# 20260112.net
KiCad netlist of a schematic drawn in EasyEDA Pro
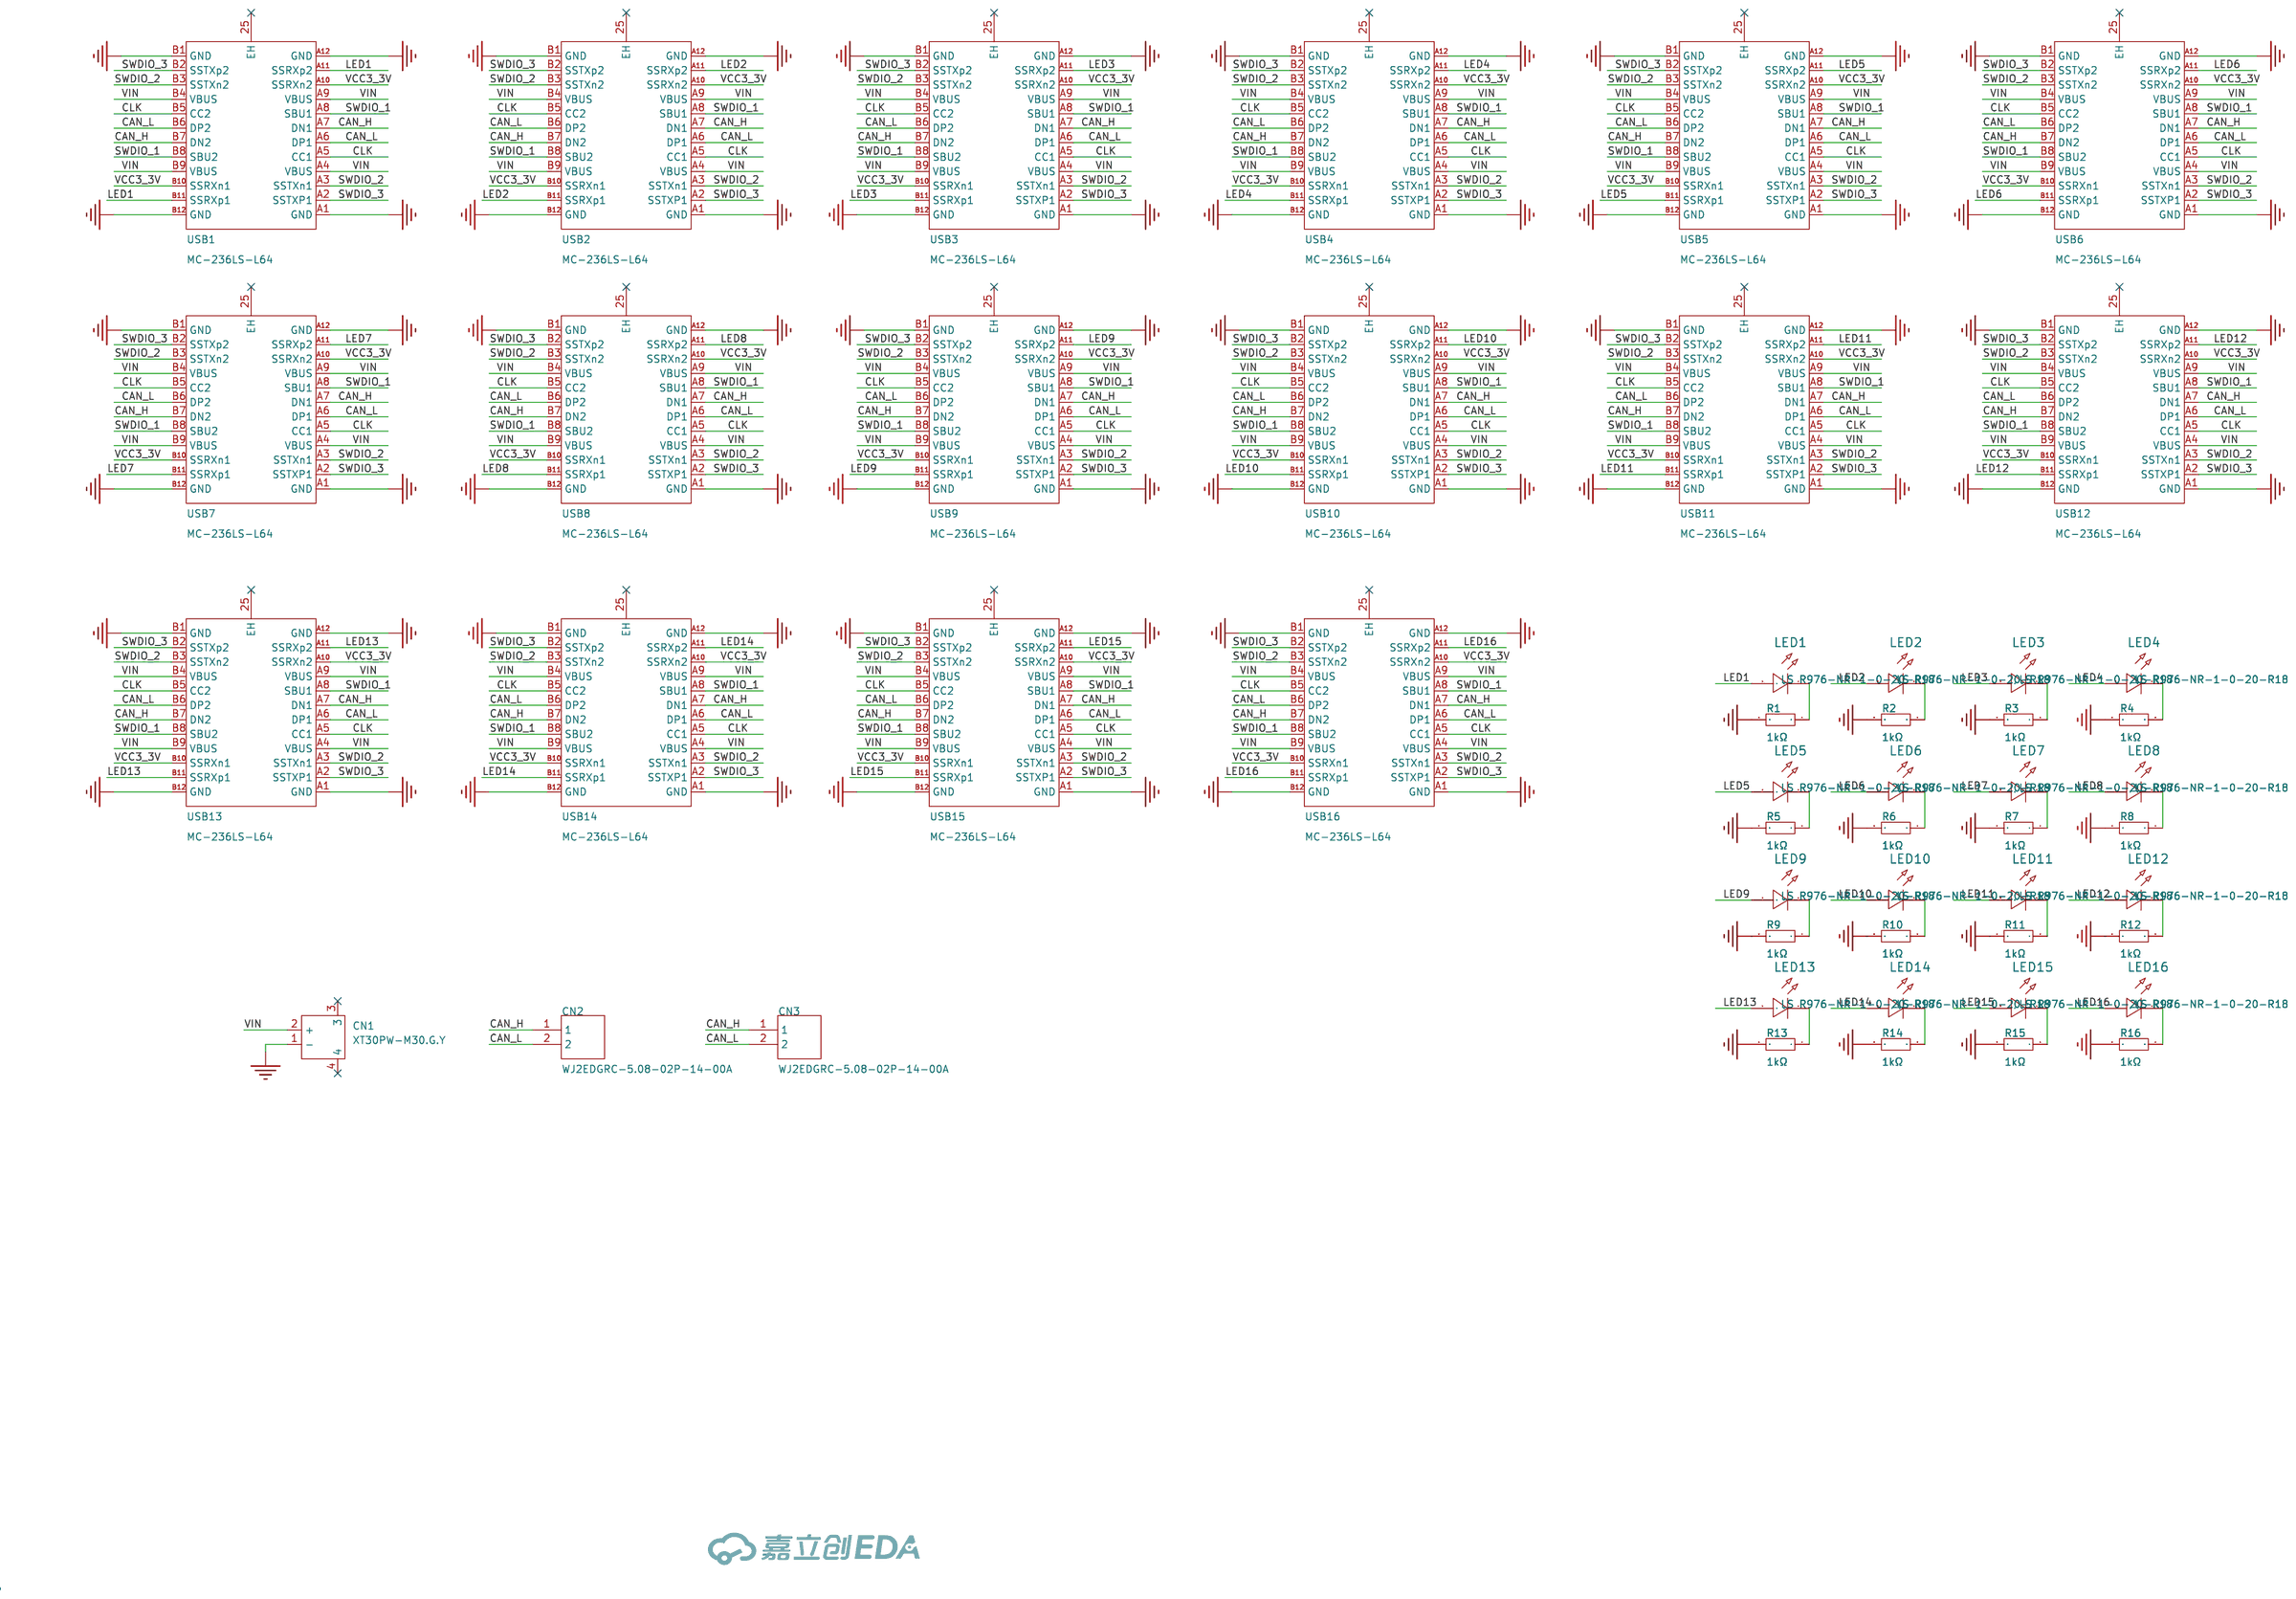
[diagram p0: schematic sheet]

(export (version "E")
  (design (tool "Eeschema 10.0.6"))
  (components
    (comp (ref "CN1")
      (value "XT30PW-M30.G.Y")
      (footprint "easyedapro:CONN-TH_XT30PW-M")
      (description "类别:-;类型1:-;")
      (fields (field (name "Manufacturer") "AMASS(艾迈斯)"))
      (libsource (lib "easyedapro") (part "XT30PW-M"))
    )
    (comp (ref "CN2")
      (value "WJ2EDGRC-5.08-02P-14-00A")
      (footprint "easyedapro:CONN-TH_2P-P5.08_WJ2EDGRC-5.08-2P")
      (fields (field (name "Manufacturer") "KANGNEX(康奈克斯电气)"))
      (libsource (lib "easyedapro") (part "WJ2EDGRC-5.08-2P"))
    )
    (comp (ref "CN3")
      (value "WJ2EDGRC-5.08-02P-14-00A")
      (footprint "easyedapro:CONN-TH_2P-P5.08_WJ2EDGRC-5.08-2P")
      (fields (field (name "Manufacturer") "KANGNEX(康奈克斯电气)"))
      (libsource (lib "easyedapro") (part "WJ2EDGRC-5.08-2P"))
    )
    (comp (ref "LED1")
      (value "LS R976-NR-1-0-20-R18")
      (footprint "easyedapro:LED_0805")
      (fields (field (name "Manufacturer") "OSRAM(欧司朗)"))
      (libsource (lib "easyedapro") (part "LED_R"))
    )
    (comp (ref "LED2")
      (value "LS R976-NR-1-0-20-R18")
      (footprint "easyedapro:LED_0805")
      (fields (field (name "Manufacturer") "OSRAM(欧司朗)"))
      (libsource (lib "easyedapro") (part "LED_R"))
    )
    (comp (ref "LED3")
      (value "LS R976-NR-1-0-20-R18")
      (footprint "easyedapro:LED_0805")
      (fields (field (name "Manufacturer") "OSRAM(欧司朗)"))
      (libsource (lib "easyedapro") (part "LED_R"))
    )
    (comp (ref "LED4")
      (value "LS R976-NR-1-0-20-R18")
      (footprint "easyedapro:LED_0805")
      (fields (field (name "Manufacturer") "OSRAM(欧司朗)"))
      (libsource (lib "easyedapro") (part "LED_R"))
    )
    (comp (ref "LED5")
      (value "LS R976-NR-1-0-20-R18")
      (footprint "easyedapro:LED_0805")
      (fields (field (name "Manufacturer") "OSRAM(欧司朗)"))
      (libsource (lib "easyedapro") (part "LED_R"))
    )
    (comp (ref "LED6")
      (value "LS R976-NR-1-0-20-R18")
      (footprint "easyedapro:LED_0805")
      (fields (field (name "Manufacturer") "OSRAM(欧司朗)"))
      (libsource (lib "easyedapro") (part "LED_R"))
    )
    (comp (ref "LED7")
      (value "LS R976-NR-1-0-20-R18")
      (footprint "easyedapro:LED_0805")
      (fields (field (name "Manufacturer") "OSRAM(欧司朗)"))
      (libsource (lib "easyedapro") (part "LED_R"))
    )
    (comp (ref "LED8")
      (value "LS R976-NR-1-0-20-R18")
      (footprint "easyedapro:LED_0805")
      (fields (field (name "Manufacturer") "OSRAM(欧司朗)"))
      (libsource (lib "easyedapro") (part "LED_R"))
    )
    (comp (ref "LED9")
      (value "LS R976-NR-1-0-20-R18")
      (footprint "easyedapro:LED_0805")
      (fields (field (name "Manufacturer") "OSRAM(欧司朗)"))
      (libsource (lib "easyedapro") (part "LED_R"))
    )
    (comp (ref "LED10")
      (value "LS R976-NR-1-0-20-R18")
      (footprint "easyedapro:LED_0805")
      (fields (field (name "Manufacturer") "OSRAM(欧司朗)"))
      (libsource (lib "easyedapro") (part "LED_R"))
    )
    (comp (ref "LED11")
      (value "LS R976-NR-1-0-20-R18")
      (footprint "easyedapro:LED_0805")
      (fields (field (name "Manufacturer") "OSRAM(欧司朗)"))
      (libsource (lib "easyedapro") (part "LED_R"))
    )
    (comp (ref "LED12")
      (value "LS R976-NR-1-0-20-R18")
      (footprint "easyedapro:LED_0805")
      (fields (field (name "Manufacturer") "OSRAM(欧司朗)"))
      (libsource (lib "easyedapro") (part "LED_R"))
    )
    (comp (ref "LED13")
      (value "LS R976-NR-1-0-20-R18")
      (footprint "easyedapro:LED_0805")
      (fields (field (name "Manufacturer") "OSRAM(欧司朗)"))
      (libsource (lib "easyedapro") (part "LED_R"))
    )
    (comp (ref "LED14")
      (value "LS R976-NR-1-0-20-R18")
      (footprint "easyedapro:LED_0805")
      (fields (field (name "Manufacturer") "OSRAM(欧司朗)"))
      (libsource (lib "easyedapro") (part "LED_R"))
    )
    (comp (ref "LED15")
      (value "LS R976-NR-1-0-20-R18")
      (footprint "easyedapro:LED_0805")
      (fields (field (name "Manufacturer") "OSRAM(欧司朗)"))
      (libsource (lib "easyedapro") (part "LED_R"))
    )
    (comp (ref "LED16")
      (value "LS R976-NR-1-0-20-R18")
      (footprint "easyedapro:LED_0805")
      (fields (field (name "Manufacturer") "OSRAM(欧司朗)"))
      (libsource (lib "easyedapro") (part "LED_R"))
    )
    (comp (ref "R1")
      (value "1kΩ")
      (footprint "easyedapro:R0805")
      (fields
        (field (name "Manufacturer Part") "0805W8F1001T5E")
        (field (name "Manufacturer") "UNI-ROYAL(厚声)")
      )
      (libsource (lib "easyedapro") (part "电阻"))
    )
    (comp (ref "R2")
      (value "1kΩ")
      (footprint "easyedapro:R0805")
      (fields
        (field (name "Manufacturer Part") "0805W8F1001T5E")
        (field (name "Manufacturer") "UNI-ROYAL(厚声)")
      )
      (libsource (lib "easyedapro") (part "电阻"))
    )
    (comp (ref "R3")
      (value "1kΩ")
      (footprint "easyedapro:R0805")
      (fields
        (field (name "Manufacturer Part") "0805W8F1001T5E")
        (field (name "Manufacturer") "UNI-ROYAL(厚声)")
      )
      (libsource (lib "easyedapro") (part "电阻"))
    )
    (comp (ref "R4")
      (value "1kΩ")
      (footprint "easyedapro:R0805")
      (fields
        (field (name "Manufacturer Part") "0805W8F1001T5E")
        (field (name "Manufacturer") "UNI-ROYAL(厚声)")
      )
      (libsource (lib "easyedapro") (part "电阻"))
    )
    (comp (ref "R5")
      (value "1kΩ")
      (footprint "easyedapro:R0805")
      (fields
        (field (name "Manufacturer Part") "0805W8F1001T5E")
        (field (name "Manufacturer") "UNI-ROYAL(厚声)")
      )
      (libsource (lib "easyedapro") (part "电阻"))
    )
    (comp (ref "R6")
      (value "1kΩ")
      (footprint "easyedapro:R0805")
      (fields
        (field (name "Manufacturer Part") "0805W8F1001T5E")
        (field (name "Manufacturer") "UNI-ROYAL(厚声)")
      )
      (libsource (lib "easyedapro") (part "电阻"))
    )
    (comp (ref "R7")
      (value "1kΩ")
      (footprint "easyedapro:R0805")
      (fields
        (field (name "Manufacturer Part") "0805W8F1001T5E")
        (field (name "Manufacturer") "UNI-ROYAL(厚声)")
      )
      (libsource (lib "easyedapro") (part "电阻"))
    )
    (comp (ref "R8")
      (value "1kΩ")
      (footprint "easyedapro:R0805")
      (fields
        (field (name "Manufacturer Part") "0805W8F1001T5E")
        (field (name "Manufacturer") "UNI-ROYAL(厚声)")
      )
      (libsource (lib "easyedapro") (part "电阻"))
    )
    (comp (ref "R9")
      (value "1kΩ")
      (footprint "easyedapro:R0805")
      (fields
        (field (name "Manufacturer Part") "0805W8F1001T5E")
        (field (name "Manufacturer") "UNI-ROYAL(厚声)")
      )
      (libsource (lib "easyedapro") (part "电阻"))
    )
    (comp (ref "R10")
      (value "1kΩ")
      (footprint "easyedapro:R0805")
      (fields
        (field (name "Manufacturer Part") "0805W8F1001T5E")
        (field (name "Manufacturer") "UNI-ROYAL(厚声)")
      )
      (libsource (lib "easyedapro") (part "电阻"))
    )
    (comp (ref "R11")
      (value "1kΩ")
      (footprint "easyedapro:R0805")
      (fields
        (field (name "Manufacturer Part") "0805W8F1001T5E")
        (field (name "Manufacturer") "UNI-ROYAL(厚声)")
      )
      (libsource (lib "easyedapro") (part "电阻"))
    )
    (comp (ref "R12")
      (value "1kΩ")
      (footprint "easyedapro:R0805")
      (fields
        (field (name "Manufacturer Part") "0805W8F1001T5E")
        (field (name "Manufacturer") "UNI-ROYAL(厚声)")
      )
      (libsource (lib "easyedapro") (part "电阻"))
    )
    (comp (ref "R13")
      (value "1kΩ")
      (footprint "easyedapro:R0805")
      (fields
        (field (name "Manufacturer Part") "0805W8F1001T5E")
        (field (name "Manufacturer") "UNI-ROYAL(厚声)")
      )
      (libsource (lib "easyedapro") (part "电阻"))
    )
    (comp (ref "R14")
      (value "1kΩ")
      (footprint "easyedapro:R0805")
      (fields
        (field (name "Manufacturer Part") "0805W8F1001T5E")
        (field (name "Manufacturer") "UNI-ROYAL(厚声)")
      )
      (libsource (lib "easyedapro") (part "电阻"))
    )
    (comp (ref "R15")
      (value "1kΩ")
      (footprint "easyedapro:R0805")
      (fields
        (field (name "Manufacturer Part") "0805W8F1001T5E")
        (field (name "Manufacturer") "UNI-ROYAL(厚声)")
      )
      (libsource (lib "easyedapro") (part "电阻"))
    )
    (comp (ref "R16")
      (value "1kΩ")
      (footprint "easyedapro:R0805")
      (fields
        (field (name "Manufacturer Part") "0805W8F1001T5E")
        (field (name "Manufacturer") "UNI-ROYAL(厚声)")
      )
      (libsource (lib "easyedapro") (part "电阻"))
    )
    (comp (ref "USB1")
      (value "MC-236LS-L64")
      (footprint "easyedapro:TYPE-C-USB-SMD_TYPE-C-31-M-06")
      (description "连接器类型:Type-C;协议标准:USB 3.1;公母:母;安装方式:立贴;触点数量:24P;端口数量:1;额定电流 - 电源:5A;工作温度:-25°C~+85°C;")
      (fields (field (name "Manufacturer") "HANBO(汉博)"))
      (libsource (lib "easyedapro") (part "MC-236LS-L64"))
    )
    (comp (ref "USB2")
      (value "MC-236LS-L64")
      (footprint "easyedapro:TYPE-C-USB-SMD_TYPE-C-31-M-06")
      (description "连接器类型:Type-C;协议标准:USB 3.1;公母:母;安装方式:立贴;触点数量:24P;端口数量:1;额定电流 - 电源:5A;工作温度:-25°C~+85°C;")
      (fields (field (name "Manufacturer") "HANBO(汉博)"))
      (libsource (lib "easyedapro") (part "MC-236LS-L64"))
    )
    (comp (ref "USB3")
      (value "MC-236LS-L64")
      (footprint "easyedapro:TYPE-C-USB-SMD_TYPE-C-31-M-06")
      (description "连接器类型:Type-C;协议标准:USB 3.1;公母:母;安装方式:立贴;触点数量:24P;端口数量:1;额定电流 - 电源:5A;工作温度:-25°C~+85°C;")
      (fields (field (name "Manufacturer") "HANBO(汉博)"))
      (libsource (lib "easyedapro") (part "MC-236LS-L64"))
    )
    (comp (ref "USB4")
      (value "MC-236LS-L64")
      (footprint "easyedapro:TYPE-C-USB-SMD_TYPE-C-31-M-06")
      (description "连接器类型:Type-C;协议标准:USB 3.1;公母:母;安装方式:立贴;触点数量:24P;端口数量:1;额定电流 - 电源:5A;工作温度:-25°C~+85°C;")
      (fields (field (name "Manufacturer") "HANBO(汉博)"))
      (libsource (lib "easyedapro") (part "MC-236LS-L64"))
    )
    (comp (ref "USB5")
      (value "MC-236LS-L64")
      (footprint "easyedapro:TYPE-C-USB-SMD_TYPE-C-31-M-06")
      (description "连接器类型:Type-C;协议标准:USB 3.1;公母:母;安装方式:立贴;触点数量:24P;端口数量:1;额定电流 - 电源:5A;工作温度:-25°C~+85°C;")
      (fields (field (name "Manufacturer") "HANBO(汉博)"))
      (libsource (lib "easyedapro") (part "MC-236LS-L64"))
    )
    (comp (ref "USB6")
      (value "MC-236LS-L64")
      (footprint "easyedapro:TYPE-C-USB-SMD_TYPE-C-31-M-06")
      (description "连接器类型:Type-C;协议标准:USB 3.1;公母:母;安装方式:立贴;触点数量:24P;端口数量:1;额定电流 - 电源:5A;工作温度:-25°C~+85°C;")
      (fields (field (name "Manufacturer") "HANBO(汉博)"))
      (libsource (lib "easyedapro") (part "MC-236LS-L64"))
    )
    (comp (ref "USB7")
      (value "MC-236LS-L64")
      (footprint "easyedapro:TYPE-C-USB-SMD_TYPE-C-31-M-06")
      (description "连接器类型:Type-C;协议标准:USB 3.1;公母:母;安装方式:立贴;触点数量:24P;端口数量:1;额定电流 - 电源:5A;工作温度:-25°C~+85°C;")
      (fields (field (name "Manufacturer") "HANBO(汉博)"))
      (libsource (lib "easyedapro") (part "MC-236LS-L64"))
    )
    (comp (ref "USB8")
      (value "MC-236LS-L64")
      (footprint "easyedapro:TYPE-C-USB-SMD_TYPE-C-31-M-06")
      (description "连接器类型:Type-C;协议标准:USB 3.1;公母:母;安装方式:立贴;触点数量:24P;端口数量:1;额定电流 - 电源:5A;工作温度:-25°C~+85°C;")
      (fields (field (name "Manufacturer") "HANBO(汉博)"))
      (libsource (lib "easyedapro") (part "MC-236LS-L64"))
    )
    (comp (ref "USB9")
      (value "MC-236LS-L64")
      (footprint "easyedapro:TYPE-C-USB-SMD_TYPE-C-31-M-06")
      (description "连接器类型:Type-C;协议标准:USB 3.1;公母:母;安装方式:立贴;触点数量:24P;端口数量:1;额定电流 - 电源:5A;工作温度:-25°C~+85°C;")
      (fields (field (name "Manufacturer") "HANBO(汉博)"))
      (libsource (lib "easyedapro") (part "MC-236LS-L64"))
    )
    (comp (ref "USB10")
      (value "MC-236LS-L64")
      (footprint "easyedapro:TYPE-C-USB-SMD_TYPE-C-31-M-06")
      (description "连接器类型:Type-C;协议标准:USB 3.1;公母:母;安装方式:立贴;触点数量:24P;端口数量:1;额定电流 - 电源:5A;工作温度:-25°C~+85°C;")
      (fields (field (name "Manufacturer") "HANBO(汉博)"))
      (libsource (lib "easyedapro") (part "MC-236LS-L64"))
    )
    (comp (ref "USB11")
      (value "MC-236LS-L64")
      (footprint "easyedapro:TYPE-C-USB-SMD_TYPE-C-31-M-06")
      (description "连接器类型:Type-C;协议标准:USB 3.1;公母:母;安装方式:立贴;触点数量:24P;端口数量:1;额定电流 - 电源:5A;工作温度:-25°C~+85°C;")
      (fields (field (name "Manufacturer") "HANBO(汉博)"))
      (libsource (lib "easyedapro") (part "MC-236LS-L64"))
    )
    (comp (ref "USB12")
      (value "MC-236LS-L64")
      (footprint "easyedapro:TYPE-C-USB-SMD_TYPE-C-31-M-06")
      (description "连接器类型:Type-C;协议标准:USB 3.1;公母:母;安装方式:立贴;触点数量:24P;端口数量:1;额定电流 - 电源:5A;工作温度:-25°C~+85°C;")
      (fields (field (name "Manufacturer") "HANBO(汉博)"))
      (libsource (lib "easyedapro") (part "MC-236LS-L64"))
    )
    (comp (ref "USB13")
      (value "MC-236LS-L64")
      (footprint "easyedapro:TYPE-C-USB-SMD_TYPE-C-31-M-06")
      (description "连接器类型:Type-C;协议标准:USB 3.1;公母:母;安装方式:立贴;触点数量:24P;端口数量:1;额定电流 - 电源:5A;工作温度:-25°C~+85°C;")
      (fields (field (name "Manufacturer") "HANBO(汉博)"))
      (libsource (lib "easyedapro") (part "MC-236LS-L64"))
    )
    (comp (ref "USB14")
      (value "MC-236LS-L64")
      (footprint "easyedapro:TYPE-C-USB-SMD_TYPE-C-31-M-06")
      (description "连接器类型:Type-C;协议标准:USB 3.1;公母:母;安装方式:立贴;触点数量:24P;端口数量:1;额定电流 - 电源:5A;工作温度:-25°C~+85°C;")
      (fields (field (name "Manufacturer") "HANBO(汉博)"))
      (libsource (lib "easyedapro") (part "MC-236LS-L64"))
    )
    (comp (ref "USB15")
      (value "MC-236LS-L64")
      (footprint "easyedapro:TYPE-C-USB-SMD_TYPE-C-31-M-06")
      (description "连接器类型:Type-C;协议标准:USB 3.1;公母:母;安装方式:立贴;触点数量:24P;端口数量:1;额定电流 - 电源:5A;工作温度:-25°C~+85°C;")
      (fields (field (name "Manufacturer") "HANBO(汉博)"))
      (libsource (lib "easyedapro") (part "MC-236LS-L64"))
    )
    (comp (ref "USB16")
      (value "MC-236LS-L64")
      (footprint "easyedapro:TYPE-C-USB-SMD_TYPE-C-31-M-06")
      (description "连接器类型:Type-C;协议标准:USB 3.1;公母:母;安装方式:立贴;触点数量:24P;端口数量:1;额定电流 - 电源:5A;工作温度:-25°C~+85°C;")
      (fields (field (name "Manufacturer") "HANBO(汉博)"))
      (libsource (lib "easyedapro") (part "MC-236LS-L64"))
    )
  )
  (nets
    (net (code "1") (name "/CAN_H") (class "Default")
      (node (ref "CN2") (pin "1") (pinfunction "1_1") (pintype "unspecified"))
      (node (ref "CN3") (pin "1") (pinfunction "1_1") (pintype "unspecified"))
      (node (ref "USB1") (pin "A7") (pinfunction "DN1_A7") (pintype "unspecified"))
      (node (ref "USB1") (pin "B7") (pinfunction "DN2_B7") (pintype "unspecified"))
      (node (ref "USB10") (pin "A7") (pinfunction "DN1_A7") (pintype "unspecified"))
      (node (ref "USB10") (pin "B7") (pinfunction "DN2_B7") (pintype "unspecified"))
      (node (ref "USB11") (pin "A7") (pinfunction "DN1_A7") (pintype "unspecified"))
      (node (ref "USB11") (pin "B7") (pinfunction "DN2_B7") (pintype "unspecified"))
      (node (ref "USB12") (pin "A7") (pinfunction "DN1_A7") (pintype "unspecified"))
      (node (ref "USB12") (pin "B7") (pinfunction "DN2_B7") (pintype "unspecified"))
      (node (ref "USB13") (pin "A7") (pinfunction "DN1_A7") (pintype "unspecified"))
      (node (ref "USB13") (pin "B7") (pinfunction "DN2_B7") (pintype "unspecified"))
      (node (ref "USB14") (pin "A7") (pinfunction "DN1_A7") (pintype "unspecified"))
      (node (ref "USB14") (pin "B7") (pinfunction "DN2_B7") (pintype "unspecified"))
      (node (ref "USB15") (pin "A7") (pinfunction "DN1_A7") (pintype "unspecified"))
      (node (ref "USB15") (pin "B7") (pinfunction "DN2_B7") (pintype "unspecified"))
      (node (ref "USB16") (pin "A7") (pinfunction "DN1_A7") (pintype "unspecified"))
      (node (ref "USB16") (pin "B7") (pinfunction "DN2_B7") (pintype "unspecified"))
      (node (ref "USB2") (pin "A7") (pinfunction "DN1_A7") (pintype "unspecified"))
      (node (ref "USB2") (pin "B7") (pinfunction "DN2_B7") (pintype "unspecified"))
      (node (ref "USB3") (pin "A7") (pinfunction "DN1_A7") (pintype "unspecified"))
      (node (ref "USB3") (pin "B7") (pinfunction "DN2_B7") (pintype "unspecified"))
      (node (ref "USB4") (pin "A7") (pinfunction "DN1_A7") (pintype "unspecified"))
      (node (ref "USB4") (pin "B7") (pinfunction "DN2_B7") (pintype "unspecified"))
      (node (ref "USB5") (pin "A7") (pinfunction "DN1_A7") (pintype "unspecified"))
      (node (ref "USB5") (pin "B7") (pinfunction "DN2_B7") (pintype "unspecified"))
      (node (ref "USB6") (pin "A7") (pinfunction "DN1_A7") (pintype "unspecified"))
      (node (ref "USB6") (pin "B7") (pinfunction "DN2_B7") (pintype "unspecified"))
      (node (ref "USB7") (pin "A7") (pinfunction "DN1_A7") (pintype "unspecified"))
      (node (ref "USB7") (pin "B7") (pinfunction "DN2_B7") (pintype "unspecified"))
      (node (ref "USB8") (pin "A7") (pinfunction "DN1_A7") (pintype "unspecified"))
      (node (ref "USB8") (pin "B7") (pinfunction "DN2_B7") (pintype "unspecified"))
      (node (ref "USB9") (pin "A7") (pinfunction "DN1_A7") (pintype "unspecified"))
      (node (ref "USB9") (pin "B7") (pinfunction "DN2_B7") (pintype "unspecified"))
    )
    (net (code "2") (name "/CAN_L") (class "Default")
      (node (ref "CN2") (pin "2") (pinfunction "2_2") (pintype "unspecified"))
      (node (ref "CN3") (pin "2") (pinfunction "2_2") (pintype "unspecified"))
      (node (ref "USB1") (pin "A6") (pinfunction "DP1_A6") (pintype "unspecified"))
      (node (ref "USB1") (pin "B6") (pinfunction "DP2_B6") (pintype "unspecified"))
      (node (ref "USB10") (pin "A6") (pinfunction "DP1_A6") (pintype "unspecified"))
      (node (ref "USB10") (pin "B6") (pinfunction "DP2_B6") (pintype "unspecified"))
      (node (ref "USB11") (pin "A6") (pinfunction "DP1_A6") (pintype "unspecified"))
      (node (ref "USB11") (pin "B6") (pinfunction "DP2_B6") (pintype "unspecified"))
      (node (ref "USB12") (pin "A6") (pinfunction "DP1_A6") (pintype "unspecified"))
      (node (ref "USB12") (pin "B6") (pinfunction "DP2_B6") (pintype "unspecified"))
      (node (ref "USB13") (pin "A6") (pinfunction "DP1_A6") (pintype "unspecified"))
      (node (ref "USB13") (pin "B6") (pinfunction "DP2_B6") (pintype "unspecified"))
      (node (ref "USB14") (pin "A6") (pinfunction "DP1_A6") (pintype "unspecified"))
      (node (ref "USB14") (pin "B6") (pinfunction "DP2_B6") (pintype "unspecified"))
      (node (ref "USB15") (pin "A6") (pinfunction "DP1_A6") (pintype "unspecified"))
      (node (ref "USB15") (pin "B6") (pinfunction "DP2_B6") (pintype "unspecified"))
      (node (ref "USB16") (pin "A6") (pinfunction "DP1_A6") (pintype "unspecified"))
      (node (ref "USB16") (pin "B6") (pinfunction "DP2_B6") (pintype "unspecified"))
      (node (ref "USB2") (pin "A6") (pinfunction "DP1_A6") (pintype "unspecified"))
      (node (ref "USB2") (pin "B6") (pinfunction "DP2_B6") (pintype "unspecified"))
      (node (ref "USB3") (pin "A6") (pinfunction "DP1_A6") (pintype "unspecified"))
      (node (ref "USB3") (pin "B6") (pinfunction "DP2_B6") (pintype "unspecified"))
      (node (ref "USB4") (pin "A6") (pinfunction "DP1_A6") (pintype "unspecified"))
      (node (ref "USB4") (pin "B6") (pinfunction "DP2_B6") (pintype "unspecified"))
      (node (ref "USB5") (pin "A6") (pinfunction "DP1_A6") (pintype "unspecified"))
      (node (ref "USB5") (pin "B6") (pinfunction "DP2_B6") (pintype "unspecified"))
      (node (ref "USB6") (pin "A6") (pinfunction "DP1_A6") (pintype "unspecified"))
      (node (ref "USB6") (pin "B6") (pinfunction "DP2_B6") (pintype "unspecified"))
      (node (ref "USB7") (pin "A6") (pinfunction "DP1_A6") (pintype "unspecified"))
      (node (ref "USB7") (pin "B6") (pinfunction "DP2_B6") (pintype "unspecified"))
      (node (ref "USB8") (pin "A6") (pinfunction "DP1_A6") (pintype "unspecified"))
      (node (ref "USB8") (pin "B6") (pinfunction "DP2_B6") (pintype "unspecified"))
      (node (ref "USB9") (pin "A6") (pinfunction "DP1_A6") (pintype "unspecified"))
      (node (ref "USB9") (pin "B6") (pinfunction "DP2_B6") (pintype "unspecified"))
    )
    (net (code "3") (name "/CLK") (class "Default")
      (node (ref "USB1") (pin "A5") (pinfunction "CC1_A5") (pintype "unspecified"))
      (node (ref "USB1") (pin "B5") (pinfunction "CC2_B5") (pintype "unspecified"))
      (node (ref "USB10") (pin "A5") (pinfunction "CC1_A5") (pintype "unspecified"))
      (node (ref "USB10") (pin "B5") (pinfunction "CC2_B5") (pintype "unspecified"))
      (node (ref "USB11") (pin "A5") (pinfunction "CC1_A5") (pintype "unspecified"))
      (node (ref "USB11") (pin "B5") (pinfunction "CC2_B5") (pintype "unspecified"))
      (node (ref "USB12") (pin "A5") (pinfunction "CC1_A5") (pintype "unspecified"))
      (node (ref "USB12") (pin "B5") (pinfunction "CC2_B5") (pintype "unspecified"))
      (node (ref "USB13") (pin "A5") (pinfunction "CC1_A5") (pintype "unspecified"))
      (node (ref "USB13") (pin "B5") (pinfunction "CC2_B5") (pintype "unspecified"))
      (node (ref "USB14") (pin "A5") (pinfunction "CC1_A5") (pintype "unspecified"))
      (node (ref "USB14") (pin "B5") (pinfunction "CC2_B5") (pintype "unspecified"))
      (node (ref "USB15") (pin "A5") (pinfunction "CC1_A5") (pintype "unspecified"))
      (node (ref "USB15") (pin "B5") (pinfunction "CC2_B5") (pintype "unspecified"))
      (node (ref "USB16") (pin "A5") (pinfunction "CC1_A5") (pintype "unspecified"))
      (node (ref "USB16") (pin "B5") (pinfunction "CC2_B5") (pintype "unspecified"))
      (node (ref "USB2") (pin "A5") (pinfunction "CC1_A5") (pintype "unspecified"))
      (node (ref "USB2") (pin "B5") (pinfunction "CC2_B5") (pintype "unspecified"))
      (node (ref "USB3") (pin "A5") (pinfunction "CC1_A5") (pintype "unspecified"))
      (node (ref "USB3") (pin "B5") (pinfunction "CC2_B5") (pintype "unspecified"))
      (node (ref "USB4") (pin "A5") (pinfunction "CC1_A5") (pintype "unspecified"))
      (node (ref "USB4") (pin "B5") (pinfunction "CC2_B5") (pintype "unspecified"))
      (node (ref "USB5") (pin "A5") (pinfunction "CC1_A5") (pintype "unspecified"))
      (node (ref "USB5") (pin "B5") (pinfunction "CC2_B5") (pintype "unspecified"))
      (node (ref "USB6") (pin "A5") (pinfunction "CC1_A5") (pintype "unspecified"))
      (node (ref "USB6") (pin "B5") (pinfunction "CC2_B5") (pintype "unspecified"))
      (node (ref "USB7") (pin "A5") (pinfunction "CC1_A5") (pintype "unspecified"))
      (node (ref "USB7") (pin "B5") (pinfunction "CC2_B5") (pintype "unspecified"))
      (node (ref "USB8") (pin "A5") (pinfunction "CC1_A5") (pintype "unspecified"))
      (node (ref "USB8") (pin "B5") (pinfunction "CC2_B5") (pintype "unspecified"))
      (node (ref "USB9") (pin "A5") (pinfunction "CC1_A5") (pintype "unspecified"))
      (node (ref "USB9") (pin "B5") (pinfunction "CC2_B5") (pintype "unspecified"))
    )
    (net (code "4") (name "/LED1") (class "Default")
      (node (ref "LED1") (pin "2") (pinfunction "A_2") (pintype "input"))
      (node (ref "USB1") (pin "A11") (pinfunction "SSRXp2_A11") (pintype "unspecified"))
      (node (ref "USB1") (pin "B11") (pinfunction "SSRXp1_B11") (pintype "unspecified"))
    )
    (net (code "5") (name "/LED2") (class "Default")
      (node (ref "LED2") (pin "2") (pinfunction "A_2") (pintype "input"))
      (node (ref "USB2") (pin "A11") (pinfunction "SSRXp2_A11") (pintype "unspecified"))
      (node (ref "USB2") (pin "B11") (pinfunction "SSRXp1_B11") (pintype "unspecified"))
    )
    (net (code "6") (name "/LED3") (class "Default")
      (node (ref "LED3") (pin "2") (pinfunction "A_2") (pintype "input"))
      (node (ref "USB3") (pin "A11") (pinfunction "SSRXp2_A11") (pintype "unspecified"))
      (node (ref "USB3") (pin "B11") (pinfunction "SSRXp1_B11") (pintype "unspecified"))
    )
    (net (code "7") (name "/LED4") (class "Default")
      (node (ref "LED4") (pin "2") (pinfunction "A_2") (pintype "input"))
      (node (ref "USB4") (pin "A11") (pinfunction "SSRXp2_A11") (pintype "unspecified"))
      (node (ref "USB4") (pin "B11") (pinfunction "SSRXp1_B11") (pintype "unspecified"))
    )
    (net (code "8") (name "/LED5") (class "Default")
      (node (ref "LED5") (pin "2") (pinfunction "A_2") (pintype "input"))
      (node (ref "USB5") (pin "A11") (pinfunction "SSRXp2_A11") (pintype "unspecified"))
      (node (ref "USB5") (pin "B11") (pinfunction "SSRXp1_B11") (pintype "unspecified"))
    )
    (net (code "9") (name "/LED6") (class "Default")
      (node (ref "LED6") (pin "2") (pinfunction "A_2") (pintype "input"))
      (node (ref "USB6") (pin "A11") (pinfunction "SSRXp2_A11") (pintype "unspecified"))
      (node (ref "USB6") (pin "B11") (pinfunction "SSRXp1_B11") (pintype "unspecified"))
    )
    (net (code "10") (name "/LED7") (class "Default")
      (node (ref "LED7") (pin "2") (pinfunction "A_2") (pintype "input"))
      (node (ref "USB7") (pin "A11") (pinfunction "SSRXp2_A11") (pintype "unspecified"))
      (node (ref "USB7") (pin "B11") (pinfunction "SSRXp1_B11") (pintype "unspecified"))
    )
    (net (code "11") (name "/LED8") (class "Default")
      (node (ref "LED8") (pin "2") (pinfunction "A_2") (pintype "input"))
      (node (ref "USB8") (pin "A11") (pinfunction "SSRXp2_A11") (pintype "unspecified"))
      (node (ref "USB8") (pin "B11") (pinfunction "SSRXp1_B11") (pintype "unspecified"))
    )
    (net (code "12") (name "/LED9") (class "Default")
      (node (ref "LED9") (pin "2") (pinfunction "A_2") (pintype "input"))
      (node (ref "USB9") (pin "A11") (pinfunction "SSRXp2_A11") (pintype "unspecified"))
      (node (ref "USB9") (pin "B11") (pinfunction "SSRXp1_B11") (pintype "unspecified"))
    )
    (net (code "13") (name "/LED10") (class "Default")
      (node (ref "LED10") (pin "2") (pinfunction "A_2") (pintype "input"))
      (node (ref "USB10") (pin "A11") (pinfunction "SSRXp2_A11") (pintype "unspecified"))
      (node (ref "USB10") (pin "B11") (pinfunction "SSRXp1_B11") (pintype "unspecified"))
    )
    (net (code "14") (name "/LED11") (class "Default")
      (node (ref "LED11") (pin "2") (pinfunction "A_2") (pintype "input"))
      (node (ref "USB11") (pin "A11") (pinfunction "SSRXp2_A11") (pintype "unspecified"))
      (node (ref "USB11") (pin "B11") (pinfunction "SSRXp1_B11") (pintype "unspecified"))
    )
    (net (code "15") (name "/LED12") (class "Default")
      (node (ref "LED12") (pin "2") (pinfunction "A_2") (pintype "input"))
      (node (ref "USB12") (pin "A11") (pinfunction "SSRXp2_A11") (pintype "unspecified"))
      (node (ref "USB12") (pin "B11") (pinfunction "SSRXp1_B11") (pintype "unspecified"))
    )
    (net (code "16") (name "/LED13") (class "Default")
      (node (ref "LED13") (pin "2") (pinfunction "A_2") (pintype "input"))
      (node (ref "USB13") (pin "A11") (pinfunction "SSRXp2_A11") (pintype "unspecified"))
      (node (ref "USB13") (pin "B11") (pinfunction "SSRXp1_B11") (pintype "unspecified"))
    )
    (net (code "17") (name "/LED14") (class "Default")
      (node (ref "LED14") (pin "2") (pinfunction "A_2") (pintype "input"))
      (node (ref "USB14") (pin "A11") (pinfunction "SSRXp2_A11") (pintype "unspecified"))
      (node (ref "USB14") (pin "B11") (pinfunction "SSRXp1_B11") (pintype "unspecified"))
    )
    (net (code "18") (name "/LED15") (class "Default")
      (node (ref "LED15") (pin "2") (pinfunction "A_2") (pintype "input"))
      (node (ref "USB15") (pin "A11") (pinfunction "SSRXp2_A11") (pintype "unspecified"))
      (node (ref "USB15") (pin "B11") (pinfunction "SSRXp1_B11") (pintype "unspecified"))
    )
    (net (code "19") (name "/LED16") (class "Default")
      (node (ref "LED16") (pin "2") (pinfunction "A_2") (pintype "input"))
      (node (ref "USB16") (pin "A11") (pinfunction "SSRXp2_A11") (pintype "unspecified"))
      (node (ref "USB16") (pin "B11") (pinfunction "SSRXp1_B11") (pintype "unspecified"))
    )
    (net (code "20") (name "/SWDIO_1") (class "Default")
      (node (ref "USB1") (pin "A8") (pinfunction "SBU1_A8") (pintype "unspecified"))
      (node (ref "USB1") (pin "B8") (pinfunction "SBU2_B8") (pintype "unspecified"))
      (node (ref "USB10") (pin "A8") (pinfunction "SBU1_A8") (pintype "unspecified"))
      (node (ref "USB10") (pin "B8") (pinfunction "SBU2_B8") (pintype "unspecified"))
      (node (ref "USB11") (pin "A8") (pinfunction "SBU1_A8") (pintype "unspecified"))
      (node (ref "USB11") (pin "B8") (pinfunction "SBU2_B8") (pintype "unspecified"))
      (node (ref "USB12") (pin "A8") (pinfunction "SBU1_A8") (pintype "unspecified"))
      (node (ref "USB12") (pin "B8") (pinfunction "SBU2_B8") (pintype "unspecified"))
      (node (ref "USB13") (pin "A8") (pinfunction "SBU1_A8") (pintype "unspecified"))
      (node (ref "USB13") (pin "B8") (pinfunction "SBU2_B8") (pintype "unspecified"))
      (node (ref "USB14") (pin "A8") (pinfunction "SBU1_A8") (pintype "unspecified"))
      (node (ref "USB14") (pin "B8") (pinfunction "SBU2_B8") (pintype "unspecified"))
      (node (ref "USB15") (pin "A8") (pinfunction "SBU1_A8") (pintype "unspecified"))
      (node (ref "USB15") (pin "B8") (pinfunction "SBU2_B8") (pintype "unspecified"))
      (node (ref "USB16") (pin "A8") (pinfunction "SBU1_A8") (pintype "unspecified"))
      (node (ref "USB16") (pin "B8") (pinfunction "SBU2_B8") (pintype "unspecified"))
      (node (ref "USB2") (pin "A8") (pinfunction "SBU1_A8") (pintype "unspecified"))
      (node (ref "USB2") (pin "B8") (pinfunction "SBU2_B8") (pintype "unspecified"))
      (node (ref "USB3") (pin "A8") (pinfunction "SBU1_A8") (pintype "unspecified"))
      (node (ref "USB3") (pin "B8") (pinfunction "SBU2_B8") (pintype "unspecified"))
      (node (ref "USB4") (pin "A8") (pinfunction "SBU1_A8") (pintype "unspecified"))
      (node (ref "USB4") (pin "B8") (pinfunction "SBU2_B8") (pintype "unspecified"))
      (node (ref "USB5") (pin "A8") (pinfunction "SBU1_A8") (pintype "unspecified"))
      (node (ref "USB5") (pin "B8") (pinfunction "SBU2_B8") (pintype "unspecified"))
      (node (ref "USB6") (pin "A8") (pinfunction "SBU1_A8") (pintype "unspecified"))
      (node (ref "USB6") (pin "B8") (pinfunction "SBU2_B8") (pintype "unspecified"))
      (node (ref "USB7") (pin "A8") (pinfunction "SBU1_A8") (pintype "unspecified"))
      (node (ref "USB7") (pin "B8") (pinfunction "SBU2_B8") (pintype "unspecified"))
      (node (ref "USB8") (pin "A8") (pinfunction "SBU1_A8") (pintype "unspecified"))
      (node (ref "USB8") (pin "B8") (pinfunction "SBU2_B8") (pintype "unspecified"))
      (node (ref "USB9") (pin "A8") (pinfunction "SBU1_A8") (pintype "unspecified"))
      (node (ref "USB9") (pin "B8") (pinfunction "SBU2_B8") (pintype "unspecified"))
    )
    (net (code "21") (name "/SWDIO_2") (class "Default")
      (node (ref "USB1") (pin "A3") (pinfunction "SSTXn1_A3") (pintype "unspecified"))
      (node (ref "USB1") (pin "B3") (pinfunction "SSTXn2_B3") (pintype "unspecified"))
      (node (ref "USB10") (pin "A3") (pinfunction "SSTXn1_A3") (pintype "unspecified"))
      (node (ref "USB10") (pin "B3") (pinfunction "SSTXn2_B3") (pintype "unspecified"))
      (node (ref "USB11") (pin "A3") (pinfunction "SSTXn1_A3") (pintype "unspecified"))
      (node (ref "USB11") (pin "B3") (pinfunction "SSTXn2_B3") (pintype "unspecified"))
      (node (ref "USB12") (pin "A3") (pinfunction "SSTXn1_A3") (pintype "unspecified"))
      (node (ref "USB12") (pin "B3") (pinfunction "SSTXn2_B3") (pintype "unspecified"))
      (node (ref "USB13") (pin "A3") (pinfunction "SSTXn1_A3") (pintype "unspecified"))
      (node (ref "USB13") (pin "B3") (pinfunction "SSTXn2_B3") (pintype "unspecified"))
      (node (ref "USB14") (pin "A3") (pinfunction "SSTXn1_A3") (pintype "unspecified"))
      (node (ref "USB14") (pin "B3") (pinfunction "SSTXn2_B3") (pintype "unspecified"))
      (node (ref "USB15") (pin "A3") (pinfunction "SSTXn1_A3") (pintype "unspecified"))
      (node (ref "USB15") (pin "B3") (pinfunction "SSTXn2_B3") (pintype "unspecified"))
      (node (ref "USB16") (pin "A3") (pinfunction "SSTXn1_A3") (pintype "unspecified"))
      (node (ref "USB16") (pin "B3") (pinfunction "SSTXn2_B3") (pintype "unspecified"))
      (node (ref "USB2") (pin "A3") (pinfunction "SSTXn1_A3") (pintype "unspecified"))
      (node (ref "USB2") (pin "B3") (pinfunction "SSTXn2_B3") (pintype "unspecified"))
      (node (ref "USB3") (pin "A3") (pinfunction "SSTXn1_A3") (pintype "unspecified"))
      (node (ref "USB3") (pin "B3") (pinfunction "SSTXn2_B3") (pintype "unspecified"))
      (node (ref "USB4") (pin "A3") (pinfunction "SSTXn1_A3") (pintype "unspecified"))
      (node (ref "USB4") (pin "B3") (pinfunction "SSTXn2_B3") (pintype "unspecified"))
      (node (ref "USB5") (pin "A3") (pinfunction "SSTXn1_A3") (pintype "unspecified"))
      (node (ref "USB5") (pin "B3") (pinfunction "SSTXn2_B3") (pintype "unspecified"))
      (node (ref "USB6") (pin "A3") (pinfunction "SSTXn1_A3") (pintype "unspecified"))
      (node (ref "USB6") (pin "B3") (pinfunction "SSTXn2_B3") (pintype "unspecified"))
      (node (ref "USB7") (pin "A3") (pinfunction "SSTXn1_A3") (pintype "unspecified"))
      (node (ref "USB7") (pin "B3") (pinfunction "SSTXn2_B3") (pintype "unspecified"))
      (node (ref "USB8") (pin "A3") (pinfunction "SSTXn1_A3") (pintype "unspecified"))
      (node (ref "USB8") (pin "B3") (pinfunction "SSTXn2_B3") (pintype "unspecified"))
      (node (ref "USB9") (pin "A3") (pinfunction "SSTXn1_A3") (pintype "unspecified"))
      (node (ref "USB9") (pin "B3") (pinfunction "SSTXn2_B3") (pintype "unspecified"))
    )
    (net (code "22") (name "/SWDIO_3") (class "Default")
      (node (ref "USB1") (pin "A2") (pinfunction "SSTXP1_A2") (pintype "unspecified"))
      (node (ref "USB1") (pin "B2") (pinfunction "SSTXp2_B2") (pintype "unspecified"))
      (node (ref "USB10") (pin "A2") (pinfunction "SSTXP1_A2") (pintype "unspecified"))
      (node (ref "USB10") (pin "B2") (pinfunction "SSTXp2_B2") (pintype "unspecified"))
      (node (ref "USB11") (pin "A2") (pinfunction "SSTXP1_A2") (pintype "unspecified"))
      (node (ref "USB11") (pin "B2") (pinfunction "SSTXp2_B2") (pintype "unspecified"))
      (node (ref "USB12") (pin "A2") (pinfunction "SSTXP1_A2") (pintype "unspecified"))
      (node (ref "USB12") (pin "B2") (pinfunction "SSTXp2_B2") (pintype "unspecified"))
      (node (ref "USB13") (pin "A2") (pinfunction "SSTXP1_A2") (pintype "unspecified"))
      (node (ref "USB13") (pin "B2") (pinfunction "SSTXp2_B2") (pintype "unspecified"))
      (node (ref "USB14") (pin "A2") (pinfunction "SSTXP1_A2") (pintype "unspecified"))
      (node (ref "USB14") (pin "B2") (pinfunction "SSTXp2_B2") (pintype "unspecified"))
      (node (ref "USB15") (pin "A2") (pinfunction "SSTXP1_A2") (pintype "unspecified"))
      (node (ref "USB15") (pin "B2") (pinfunction "SSTXp2_B2") (pintype "unspecified"))
      (node (ref "USB16") (pin "A2") (pinfunction "SSTXP1_A2") (pintype "unspecified"))
      (node (ref "USB16") (pin "B2") (pinfunction "SSTXp2_B2") (pintype "unspecified"))
      (node (ref "USB2") (pin "A2") (pinfunction "SSTXP1_A2") (pintype "unspecified"))
      (node (ref "USB2") (pin "B2") (pinfunction "SSTXp2_B2") (pintype "unspecified"))
      (node (ref "USB3") (pin "A2") (pinfunction "SSTXP1_A2") (pintype "unspecified"))
      (node (ref "USB3") (pin "B2") (pinfunction "SSTXp2_B2") (pintype "unspecified"))
      (node (ref "USB4") (pin "A2") (pinfunction "SSTXP1_A2") (pintype "unspecified"))
      (node (ref "USB4") (pin "B2") (pinfunction "SSTXp2_B2") (pintype "unspecified"))
      (node (ref "USB5") (pin "A2") (pinfunction "SSTXP1_A2") (pintype "unspecified"))
      (node (ref "USB5") (pin "B2") (pinfunction "SSTXp2_B2") (pintype "unspecified"))
      (node (ref "USB6") (pin "A2") (pinfunction "SSTXP1_A2") (pintype "unspecified"))
      (node (ref "USB6") (pin "B2") (pinfunction "SSTXp2_B2") (pintype "unspecified"))
      (node (ref "USB7") (pin "A2") (pinfunction "SSTXP1_A2") (pintype "unspecified"))
      (node (ref "USB7") (pin "B2") (pinfunction "SSTXp2_B2") (pintype "unspecified"))
      (node (ref "USB8") (pin "A2") (pinfunction "SSTXP1_A2") (pintype "unspecified"))
      (node (ref "USB8") (pin "B2") (pinfunction "SSTXp2_B2") (pintype "unspecified"))
      (node (ref "USB9") (pin "A2") (pinfunction "SSTXP1_A2") (pintype "unspecified"))
      (node (ref "USB9") (pin "B2") (pinfunction "SSTXp2_B2") (pintype "unspecified"))
    )
    (net (code "23") (name "/VCC3_3V") (class "Default")
      (node (ref "USB1") (pin "A10") (pinfunction "SSRXn2_A10") (pintype "unspecified"))
      (node (ref "USB1") (pin "B10") (pinfunction "SSRXn1_B10") (pintype "unspecified"))
      (node (ref "USB10") (pin "A10") (pinfunction "SSRXn2_A10") (pintype "unspecified"))
      (node (ref "USB10") (pin "B10") (pinfunction "SSRXn1_B10") (pintype "unspecified"))
      (node (ref "USB11") (pin "A10") (pinfunction "SSRXn2_A10") (pintype "unspecified"))
      (node (ref "USB11") (pin "B10") (pinfunction "SSRXn1_B10") (pintype "unspecified"))
      (node (ref "USB12") (pin "A10") (pinfunction "SSRXn2_A10") (pintype "unspecified"))
      (node (ref "USB12") (pin "B10") (pinfunction "SSRXn1_B10") (pintype "unspecified"))
      (node (ref "USB13") (pin "A10") (pinfunction "SSRXn2_A10") (pintype "unspecified"))
      (node (ref "USB13") (pin "B10") (pinfunction "SSRXn1_B10") (pintype "unspecified"))
      (node (ref "USB14") (pin "A10") (pinfunction "SSRXn2_A10") (pintype "unspecified"))
      (node (ref "USB14") (pin "B10") (pinfunction "SSRXn1_B10") (pintype "unspecified"))
      (node (ref "USB15") (pin "A10") (pinfunction "SSRXn2_A10") (pintype "unspecified"))
      (node (ref "USB15") (pin "B10") (pinfunction "SSRXn1_B10") (pintype "unspecified"))
      (node (ref "USB16") (pin "A10") (pinfunction "SSRXn2_A10") (pintype "unspecified"))
      (node (ref "USB16") (pin "B10") (pinfunction "SSRXn1_B10") (pintype "unspecified"))
      (node (ref "USB2") (pin "A10") (pinfunction "SSRXn2_A10") (pintype "unspecified"))
      (node (ref "USB2") (pin "B10") (pinfunction "SSRXn1_B10") (pintype "unspecified"))
      (node (ref "USB3") (pin "A10") (pinfunction "SSRXn2_A10") (pintype "unspecified"))
      (node (ref "USB3") (pin "B10") (pinfunction "SSRXn1_B10") (pintype "unspecified"))
      (node (ref "USB4") (pin "A10") (pinfunction "SSRXn2_A10") (pintype "unspecified"))
      (node (ref "USB4") (pin "B10") (pinfunction "SSRXn1_B10") (pintype "unspecified"))
      (node (ref "USB5") (pin "A10") (pinfunction "SSRXn2_A10") (pintype "unspecified"))
      (node (ref "USB5") (pin "B10") (pinfunction "SSRXn1_B10") (pintype "unspecified"))
      (node (ref "USB6") (pin "A10") (pinfunction "SSRXn2_A10") (pintype "unspecified"))
      (node (ref "USB6") (pin "B10") (pinfunction "SSRXn1_B10") (pintype "unspecified"))
      (node (ref "USB7") (pin "A10") (pinfunction "SSRXn2_A10") (pintype "unspecified"))
      (node (ref "USB7") (pin "B10") (pinfunction "SSRXn1_B10") (pintype "unspecified"))
      (node (ref "USB8") (pin "A10") (pinfunction "SSRXn2_A10") (pintype "unspecified"))
      (node (ref "USB8") (pin "B10") (pinfunction "SSRXn1_B10") (pintype "unspecified"))
      (node (ref "USB9") (pin "A10") (pinfunction "SSRXn2_A10") (pintype "unspecified"))
      (node (ref "USB9") (pin "B10") (pinfunction "SSRXn1_B10") (pintype "unspecified"))
    )
    (net (code "24") (name "/VIN") (class "Default")
      (node (ref "CN1") (pin "2") (pinfunction "+_2") (pintype "unspecified"))
      (node (ref "USB1") (pin "A4") (pinfunction "VBUS_A4") (pintype "unspecified"))
      (node (ref "USB1") (pin "A9") (pinfunction "VBUS_A9") (pintype "unspecified"))
      (node (ref "USB1") (pin "B4") (pinfunction "VBUS_B4") (pintype "unspecified"))
      (node (ref "USB1") (pin "B9") (pinfunction "VBUS_B9") (pintype "unspecified"))
      (node (ref "USB10") (pin "A4") (pinfunction "VBUS_A4") (pintype "unspecified"))
      (node (ref "USB10") (pin "A9") (pinfunction "VBUS_A9") (pintype "unspecified"))
      (node (ref "USB10") (pin "B4") (pinfunction "VBUS_B4") (pintype "unspecified"))
      (node (ref "USB10") (pin "B9") (pinfunction "VBUS_B9") (pintype "unspecified"))
      (node (ref "USB11") (pin "A4") (pinfunction "VBUS_A4") (pintype "unspecified"))
      (node (ref "USB11") (pin "A9") (pinfunction "VBUS_A9") (pintype "unspecified"))
      (node (ref "USB11") (pin "B4") (pinfunction "VBUS_B4") (pintype "unspecified"))
      (node (ref "USB11") (pin "B9") (pinfunction "VBUS_B9") (pintype "unspecified"))
      (node (ref "USB12") (pin "A4") (pinfunction "VBUS_A4") (pintype "unspecified"))
      (node (ref "USB12") (pin "A9") (pinfunction "VBUS_A9") (pintype "unspecified"))
      (node (ref "USB12") (pin "B4") (pinfunction "VBUS_B4") (pintype "unspecified"))
      (node (ref "USB12") (pin "B9") (pinfunction "VBUS_B9") (pintype "unspecified"))
      (node (ref "USB13") (pin "A4") (pinfunction "VBUS_A4") (pintype "unspecified"))
      (node (ref "USB13") (pin "A9") (pinfunction "VBUS_A9") (pintype "unspecified"))
      (node (ref "USB13") (pin "B4") (pinfunction "VBUS_B4") (pintype "unspecified"))
      (node (ref "USB13") (pin "B9") (pinfunction "VBUS_B9") (pintype "unspecified"))
      (node (ref "USB14") (pin "A4") (pinfunction "VBUS_A4") (pintype "unspecified"))
      (node (ref "USB14") (pin "A9") (pinfunction "VBUS_A9") (pintype "unspecified"))
      (node (ref "USB14") (pin "B4") (pinfunction "VBUS_B4") (pintype "unspecified"))
      (node (ref "USB14") (pin "B9") (pinfunction "VBUS_B9") (pintype "unspecified"))
      (node (ref "USB15") (pin "A4") (pinfunction "VBUS_A4") (pintype "unspecified"))
      (node (ref "USB15") (pin "A9") (pinfunction "VBUS_A9") (pintype "unspecified"))
      (node (ref "USB15") (pin "B4") (pinfunction "VBUS_B4") (pintype "unspecified"))
      (node (ref "USB15") (pin "B9") (pinfunction "VBUS_B9") (pintype "unspecified"))
      (node (ref "USB16") (pin "A4") (pinfunction "VBUS_A4") (pintype "unspecified"))
      (node (ref "USB16") (pin "A9") (pinfunction "VBUS_A9") (pintype "unspecified"))
      (node (ref "USB16") (pin "B4") (pinfunction "VBUS_B4") (pintype "unspecified"))
      (node (ref "USB16") (pin "B9") (pinfunction "VBUS_B9") (pintype "unspecified"))
      (node (ref "USB2") (pin "A4") (pinfunction "VBUS_A4") (pintype "unspecified"))
      (node (ref "USB2") (pin "A9") (pinfunction "VBUS_A9") (pintype "unspecified"))
      (node (ref "USB2") (pin "B4") (pinfunction "VBUS_B4") (pintype "unspecified"))
      (node (ref "USB2") (pin "B9") (pinfunction "VBUS_B9") (pintype "unspecified"))
      (node (ref "USB3") (pin "A4") (pinfunction "VBUS_A4") (pintype "unspecified"))
      (node (ref "USB3") (pin "A9") (pinfunction "VBUS_A9") (pintype "unspecified"))
      (node (ref "USB3") (pin "B4") (pinfunction "VBUS_B4") (pintype "unspecified"))
      (node (ref "USB3") (pin "B9") (pinfunction "VBUS_B9") (pintype "unspecified"))
      (node (ref "USB4") (pin "A4") (pinfunction "VBUS_A4") (pintype "unspecified"))
      (node (ref "USB4") (pin "A9") (pinfunction "VBUS_A9") (pintype "unspecified"))
      (node (ref "USB4") (pin "B4") (pinfunction "VBUS_B4") (pintype "unspecified"))
      (node (ref "USB4") (pin "B9") (pinfunction "VBUS_B9") (pintype "unspecified"))
      (node (ref "USB5") (pin "A4") (pinfunction "VBUS_A4") (pintype "unspecified"))
      (node (ref "USB5") (pin "A9") (pinfunction "VBUS_A9") (pintype "unspecified"))
      (node (ref "USB5") (pin "B4") (pinfunction "VBUS_B4") (pintype "unspecified"))
      (node (ref "USB5") (pin "B9") (pinfunction "VBUS_B9") (pintype "unspecified"))
      (node (ref "USB6") (pin "A4") (pinfunction "VBUS_A4") (pintype "unspecified"))
      (node (ref "USB6") (pin "A9") (pinfunction "VBUS_A9") (pintype "unspecified"))
      (node (ref "USB6") (pin "B4") (pinfunction "VBUS_B4") (pintype "unspecified"))
      (node (ref "USB6") (pin "B9") (pinfunction "VBUS_B9") (pintype "unspecified"))
      (node (ref "USB7") (pin "A4") (pinfunction "VBUS_A4") (pintype "unspecified"))
      (node (ref "USB7") (pin "A9") (pinfunction "VBUS_A9") (pintype "unspecified"))
      (node (ref "USB7") (pin "B4") (pinfunction "VBUS_B4") (pintype "unspecified"))
      (node (ref "USB7") (pin "B9") (pinfunction "VBUS_B9") (pintype "unspecified"))
      (node (ref "USB8") (pin "A4") (pinfunction "VBUS_A4") (pintype "unspecified"))
      (node (ref "USB8") (pin "A9") (pinfunction "VBUS_A9") (pintype "unspecified"))
      (node (ref "USB8") (pin "B4") (pinfunction "VBUS_B4") (pintype "unspecified"))
      (node (ref "USB8") (pin "B9") (pinfunction "VBUS_B9") (pintype "unspecified"))
      (node (ref "USB9") (pin "A4") (pinfunction "VBUS_A4") (pintype "unspecified"))
      (node (ref "USB9") (pin "A9") (pinfunction "VBUS_A9") (pintype "unspecified"))
      (node (ref "USB9") (pin "B4") (pinfunction "VBUS_B4") (pintype "unspecified"))
      (node (ref "USB9") (pin "B9") (pinfunction "VBUS_B9") (pintype "unspecified"))
    )
    (net (code "25") (name "GND") (class "Default")
      (node (ref "CN1") (pin "1") (pinfunction "-_1") (pintype "unspecified"))
      (node (ref "R1") (pin "2") (pinfunction "2_2") (pintype "input"))
      (node (ref "R10") (pin "2") (pinfunction "2_2") (pintype "input"))
      (node (ref "R11") (pin "2") (pinfunction "2_2") (pintype "input"))
      (node (ref "R12") (pin "2") (pinfunction "2_2") (pintype "input"))
      (node (ref "R13") (pin "2") (pinfunction "2_2") (pintype "input"))
      (node (ref "R14") (pin "2") (pinfunction "2_2") (pintype "input"))
      (node (ref "R15") (pin "2") (pinfunction "2_2") (pintype "input"))
      (node (ref "R16") (pin "2") (pinfunction "2_2") (pintype "input"))
      (node (ref "R2") (pin "2") (pinfunction "2_2") (pintype "input"))
      (node (ref "R3") (pin "2") (pinfunction "2_2") (pintype "input"))
      (node (ref "R4") (pin "2") (pinfunction "2_2") (pintype "input"))
      (node (ref "R5") (pin "2") (pinfunction "2_2") (pintype "input"))
      (node (ref "R6") (pin "2") (pinfunction "2_2") (pintype "input"))
      (node (ref "R7") (pin "2") (pinfunction "2_2") (pintype "input"))
      (node (ref "R8") (pin "2") (pinfunction "2_2") (pintype "input"))
      (node (ref "R9") (pin "2") (pinfunction "2_2") (pintype "input"))
      (node (ref "USB1") (pin "A1") (pinfunction "GND_A1") (pintype "unspecified"))
      (node (ref "USB1") (pin "A12") (pinfunction "GND_A12") (pintype "unspecified"))
      (node (ref "USB1") (pin "B1") (pinfunction "GND_B1") (pintype "unspecified"))
      (node (ref "USB1") (pin "B12") (pinfunction "GND_B12") (pintype "unspecified"))
      (node (ref "USB10") (pin "A1") (pinfunction "GND_A1") (pintype "unspecified"))
      (node (ref "USB10") (pin "A12") (pinfunction "GND_A12") (pintype "unspecified"))
      (node (ref "USB10") (pin "B1") (pinfunction "GND_B1") (pintype "unspecified"))
      (node (ref "USB10") (pin "B12") (pinfunction "GND_B12") (pintype "unspecified"))
      (node (ref "USB11") (pin "A1") (pinfunction "GND_A1") (pintype "unspecified"))
      (node (ref "USB11") (pin "A12") (pinfunction "GND_A12") (pintype "unspecified"))
      (node (ref "USB11") (pin "B1") (pinfunction "GND_B1") (pintype "unspecified"))
      (node (ref "USB11") (pin "B12") (pinfunction "GND_B12") (pintype "unspecified"))
      (node (ref "USB12") (pin "A1") (pinfunction "GND_A1") (pintype "unspecified"))
      (node (ref "USB12") (pin "A12") (pinfunction "GND_A12") (pintype "unspecified"))
      (node (ref "USB12") (pin "B1") (pinfunction "GND_B1") (pintype "unspecified"))
      (node (ref "USB12") (pin "B12") (pinfunction "GND_B12") (pintype "unspecified"))
      (node (ref "USB13") (pin "A1") (pinfunction "GND_A1") (pintype "unspecified"))
      (node (ref "USB13") (pin "A12") (pinfunction "GND_A12") (pintype "unspecified"))
      (node (ref "USB13") (pin "B1") (pinfunction "GND_B1") (pintype "unspecified"))
      (node (ref "USB13") (pin "B12") (pinfunction "GND_B12") (pintype "unspecified"))
      (node (ref "USB14") (pin "A1") (pinfunction "GND_A1") (pintype "unspecified"))
      (node (ref "USB14") (pin "A12") (pinfunction "GND_A12") (pintype "unspecified"))
      (node (ref "USB14") (pin "B1") (pinfunction "GND_B1") (pintype "unspecified"))
      (node (ref "USB14") (pin "B12") (pinfunction "GND_B12") (pintype "unspecified"))
      (node (ref "USB15") (pin "A1") (pinfunction "GND_A1") (pintype "unspecified"))
      (node (ref "USB15") (pin "A12") (pinfunction "GND_A12") (pintype "unspecified"))
      (node (ref "USB15") (pin "B1") (pinfunction "GND_B1") (pintype "unspecified"))
      (node (ref "USB15") (pin "B12") (pinfunction "GND_B12") (pintype "unspecified"))
      (node (ref "USB16") (pin "A1") (pinfunction "GND_A1") (pintype "unspecified"))
      (node (ref "USB16") (pin "A12") (pinfunction "GND_A12") (pintype "unspecified"))
      (node (ref "USB16") (pin "B1") (pinfunction "GND_B1") (pintype "unspecified"))
      (node (ref "USB16") (pin "B12") (pinfunction "GND_B12") (pintype "unspecified"))
      (node (ref "USB2") (pin "A1") (pinfunction "GND_A1") (pintype "unspecified"))
      (node (ref "USB2") (pin "A12") (pinfunction "GND_A12") (pintype "unspecified"))
      (node (ref "USB2") (pin "B1") (pinfunction "GND_B1") (pintype "unspecified"))
      (node (ref "USB2") (pin "B12") (pinfunction "GND_B12") (pintype "unspecified"))
      (node (ref "USB3") (pin "A1") (pinfunction "GND_A1") (pintype "unspecified"))
      (node (ref "USB3") (pin "A12") (pinfunction "GND_A12") (pintype "unspecified"))
      (node (ref "USB3") (pin "B1") (pinfunction "GND_B1") (pintype "unspecified"))
      (node (ref "USB3") (pin "B12") (pinfunction "GND_B12") (pintype "unspecified"))
      (node (ref "USB4") (pin "A1") (pinfunction "GND_A1") (pintype "unspecified"))
      (node (ref "USB4") (pin "A12") (pinfunction "GND_A12") (pintype "unspecified"))
      (node (ref "USB4") (pin "B1") (pinfunction "GND_B1") (pintype "unspecified"))
      (node (ref "USB4") (pin "B12") (pinfunction "GND_B12") (pintype "unspecified"))
      (node (ref "USB5") (pin "A1") (pinfunction "GND_A1") (pintype "unspecified"))
      (node (ref "USB5") (pin "A12") (pinfunction "GND_A12") (pintype "unspecified"))
      (node (ref "USB5") (pin "B1") (pinfunction "GND_B1") (pintype "unspecified"))
      (node (ref "USB5") (pin "B12") (pinfunction "GND_B12") (pintype "unspecified"))
      (node (ref "USB6") (pin "A1") (pinfunction "GND_A1") (pintype "unspecified"))
      (node (ref "USB6") (pin "A12") (pinfunction "GND_A12") (pintype "unspecified"))
      (node (ref "USB6") (pin "B1") (pinfunction "GND_B1") (pintype "unspecified"))
      (node (ref "USB6") (pin "B12") (pinfunction "GND_B12") (pintype "unspecified"))
      (node (ref "USB7") (pin "A1") (pinfunction "GND_A1") (pintype "unspecified"))
      (node (ref "USB7") (pin "A12") (pinfunction "GND_A12") (pintype "unspecified"))
      (node (ref "USB7") (pin "B1") (pinfunction "GND_B1") (pintype "unspecified"))
      (node (ref "USB7") (pin "B12") (pinfunction "GND_B12") (pintype "unspecified"))
      (node (ref "USB8") (pin "A1") (pinfunction "GND_A1") (pintype "unspecified"))
      (node (ref "USB8") (pin "A12") (pinfunction "GND_A12") (pintype "unspecified"))
      (node (ref "USB8") (pin "B1") (pinfunction "GND_B1") (pintype "unspecified"))
      (node (ref "USB8") (pin "B12") (pinfunction "GND_B12") (pintype "unspecified"))
      (node (ref "USB9") (pin "A1") (pinfunction "GND_A1") (pintype "unspecified"))
      (node (ref "USB9") (pin "A12") (pinfunction "GND_A12") (pintype "unspecified"))
      (node (ref "USB9") (pin "B1") (pinfunction "GND_B1") (pintype "unspecified"))
      (node (ref "USB9") (pin "B12") (pinfunction "GND_B12") (pintype "unspecified"))
    )
    (net (code "26") (name "Net-(LED1-C)") (class "Default")
      (node (ref "LED1") (pin "1") (pinfunction "C_1") (pintype "input"))
      (node (ref "R1") (pin "1") (pinfunction "1_1") (pintype "input"))
    )
    (net (code "27") (name "Net-(LED2-C)") (class "Default")
      (node (ref "LED2") (pin "1") (pinfunction "C_1") (pintype "input"))
      (node (ref "R2") (pin "1") (pinfunction "1_1") (pintype "input"))
    )
    (net (code "28") (name "Net-(LED3-C)") (class "Default")
      (node (ref "LED3") (pin "1") (pinfunction "C_1") (pintype "input"))
      (node (ref "R3") (pin "1") (pinfunction "1_1") (pintype "input"))
    )
    (net (code "29") (name "Net-(LED4-C)") (class "Default")
      (node (ref "LED4") (pin "1") (pinfunction "C_1") (pintype "input"))
      (node (ref "R4") (pin "1") (pinfunction "1_1") (pintype "input"))
    )
    (net (code "30") (name "Net-(LED5-C)") (class "Default")
      (node (ref "LED5") (pin "1") (pinfunction "C_1") (pintype "input"))
      (node (ref "R5") (pin "1") (pinfunction "1_1") (pintype "input"))
    )
    (net (code "31") (name "Net-(LED6-C)") (class "Default")
      (node (ref "LED6") (pin "1") (pinfunction "C_1") (pintype "input"))
      (node (ref "R6") (pin "1") (pinfunction "1_1") (pintype "input"))
    )
    (net (code "32") (name "Net-(LED7-C)") (class "Default")
      (node (ref "LED7") (pin "1") (pinfunction "C_1") (pintype "input"))
      (node (ref "R7") (pin "1") (pinfunction "1_1") (pintype "input"))
    )
    (net (code "33") (name "Net-(LED8-C)") (class "Default")
      (node (ref "LED8") (pin "1") (pinfunction "C_1") (pintype "input"))
      (node (ref "R8") (pin "1") (pinfunction "1_1") (pintype "input"))
    )
    (net (code "34") (name "Net-(LED9-C)") (class "Default")
      (node (ref "LED9") (pin "1") (pinfunction "C_1") (pintype "input"))
      (node (ref "R9") (pin "1") (pinfunction "1_1") (pintype "input"))
    )
    (net (code "35") (name "Net-(LED10-C)") (class "Default")
      (node (ref "LED10") (pin "1") (pinfunction "C_1") (pintype "input"))
      (node (ref "R10") (pin "1") (pinfunction "1_1") (pintype "input"))
    )
    (net (code "36") (name "Net-(LED11-C)") (class "Default")
      (node (ref "LED11") (pin "1") (pinfunction "C_1") (pintype "input"))
      (node (ref "R11") (pin "1") (pinfunction "1_1") (pintype "input"))
    )
    (net (code "37") (name "Net-(LED12-C)") (class "Default")
      (node (ref "LED12") (pin "1") (pinfunction "C_1") (pintype "input"))
      (node (ref "R12") (pin "1") (pinfunction "1_1") (pintype "input"))
    )
    (net (code "38") (name "Net-(LED13-C)") (class "Default")
      (node (ref "LED13") (pin "1") (pinfunction "C_1") (pintype "input"))
      (node (ref "R13") (pin "1") (pinfunction "1_1") (pintype "input"))
    )
    (net (code "39") (name "Net-(LED14-C)") (class "Default")
      (node (ref "LED14") (pin "1") (pinfunction "C_1") (pintype "input"))
      (node (ref "R14") (pin "1") (pinfunction "1_1") (pintype "input"))
    )
    (net (code "40") (name "Net-(LED15-C)") (class "Default")
      (node (ref "LED15") (pin "1") (pinfunction "C_1") (pintype "input"))
      (node (ref "R15") (pin "1") (pinfunction "1_1") (pintype "input"))
    )
    (net (code "41") (name "Net-(LED16-C)") (class "Default")
      (node (ref "LED16") (pin "1") (pinfunction "C_1") (pintype "input"))
      (node (ref "R16") (pin "1") (pinfunction "1_1") (pintype "input"))
    )
    (net (code "42") (name "unconnected-(CN1-Pad3)") (class "Default")
      (node (ref "CN1") (pin "3") (pinfunction "3_3") (pintype "unspecified+no_connect"))
    )
    (net (code "43") (name "unconnected-(CN1-Pad4)") (class "Default")
      (node (ref "CN1") (pin "4") (pinfunction "4_4") (pintype "unspecified+no_connect"))
    )
    (net (code "44") (name "unconnected-(USB1-EH-Pad25)") (class "Default")
      (node (ref "USB1") (pin "25") (pinfunction "EH_25") (pintype "unspecified+no_connect"))
    )
    (net (code "45") (name "unconnected-(USB2-EH-Pad25)") (class "Default")
      (node (ref "USB2") (pin "25") (pinfunction "EH_25") (pintype "unspecified+no_connect"))
    )
    (net (code "46") (name "unconnected-(USB3-EH-Pad25)") (class "Default")
      (node (ref "USB3") (pin "25") (pinfunction "EH_25") (pintype "unspecified+no_connect"))
    )
    (net (code "47") (name "unconnected-(USB4-EH-Pad25)") (class "Default")
      (node (ref "USB4") (pin "25") (pinfunction "EH_25") (pintype "unspecified+no_connect"))
    )
    (net (code "48") (name "unconnected-(USB5-EH-Pad25)") (class "Default")
      (node (ref "USB5") (pin "25") (pinfunction "EH_25") (pintype "unspecified+no_connect"))
    )
    (net (code "49") (name "unconnected-(USB6-EH-Pad25)") (class "Default")
      (node (ref "USB6") (pin "25") (pinfunction "EH_25") (pintype "unspecified+no_connect"))
    )
    (net (code "50") (name "unconnected-(USB7-EH-Pad25)") (class "Default")
      (node (ref "USB7") (pin "25") (pinfunction "EH_25") (pintype "unspecified+no_connect"))
    )
    (net (code "51") (name "unconnected-(USB8-EH-Pad25)") (class "Default")
      (node (ref "USB8") (pin "25") (pinfunction "EH_25") (pintype "unspecified+no_connect"))
    )
    (net (code "52") (name "unconnected-(USB9-EH-Pad25)") (class "Default")
      (node (ref "USB9") (pin "25") (pinfunction "EH_25") (pintype "unspecified+no_connect"))
    )
    (net (code "53") (name "unconnected-(USB10-EH-Pad25)") (class "Default")
      (node (ref "USB10") (pin "25") (pinfunction "EH_25") (pintype "unspecified+no_connect"))
    )
    (net (code "54") (name "unconnected-(USB11-EH-Pad25)") (class "Default")
      (node (ref "USB11") (pin "25") (pinfunction "EH_25") (pintype "unspecified+no_connect"))
    )
    (net (code "55") (name "unconnected-(USB12-EH-Pad25)") (class "Default")
      (node (ref "USB12") (pin "25") (pinfunction "EH_25") (pintype "unspecified+no_connect"))
    )
    (net (code "56") (name "unconnected-(USB13-EH-Pad25)") (class "Default")
      (node (ref "USB13") (pin "25") (pinfunction "EH_25") (pintype "unspecified+no_connect"))
    )
    (net (code "57") (name "unconnected-(USB14-EH-Pad25)") (class "Default")
      (node (ref "USB14") (pin "25") (pinfunction "EH_25") (pintype "unspecified+no_connect"))
    )
    (net (code "58") (name "unconnected-(USB15-EH-Pad25)") (class "Default")
      (node (ref "USB15") (pin "25") (pinfunction "EH_25") (pintype "unspecified+no_connect"))
    )
    (net (code "59") (name "unconnected-(USB16-EH-Pad25)") (class "Default")
      (node (ref "USB16") (pin "25") (pinfunction "EH_25") (pintype "unspecified+no_connect"))
    )
  )
)
